# V7.net
KiCad netlist of a schematic drawn in Altium Designer
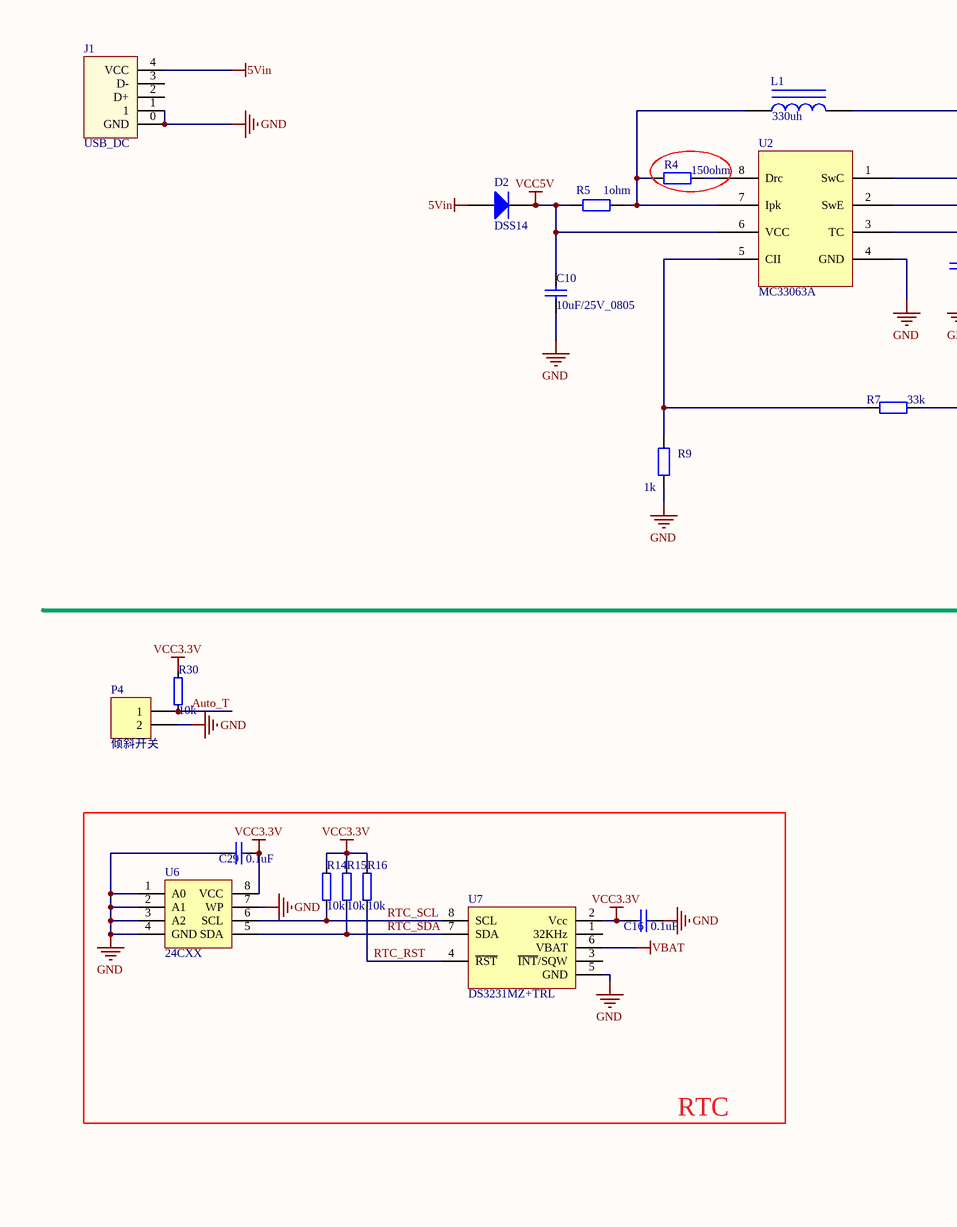
[diagram p0: V7.SchDoc, left]
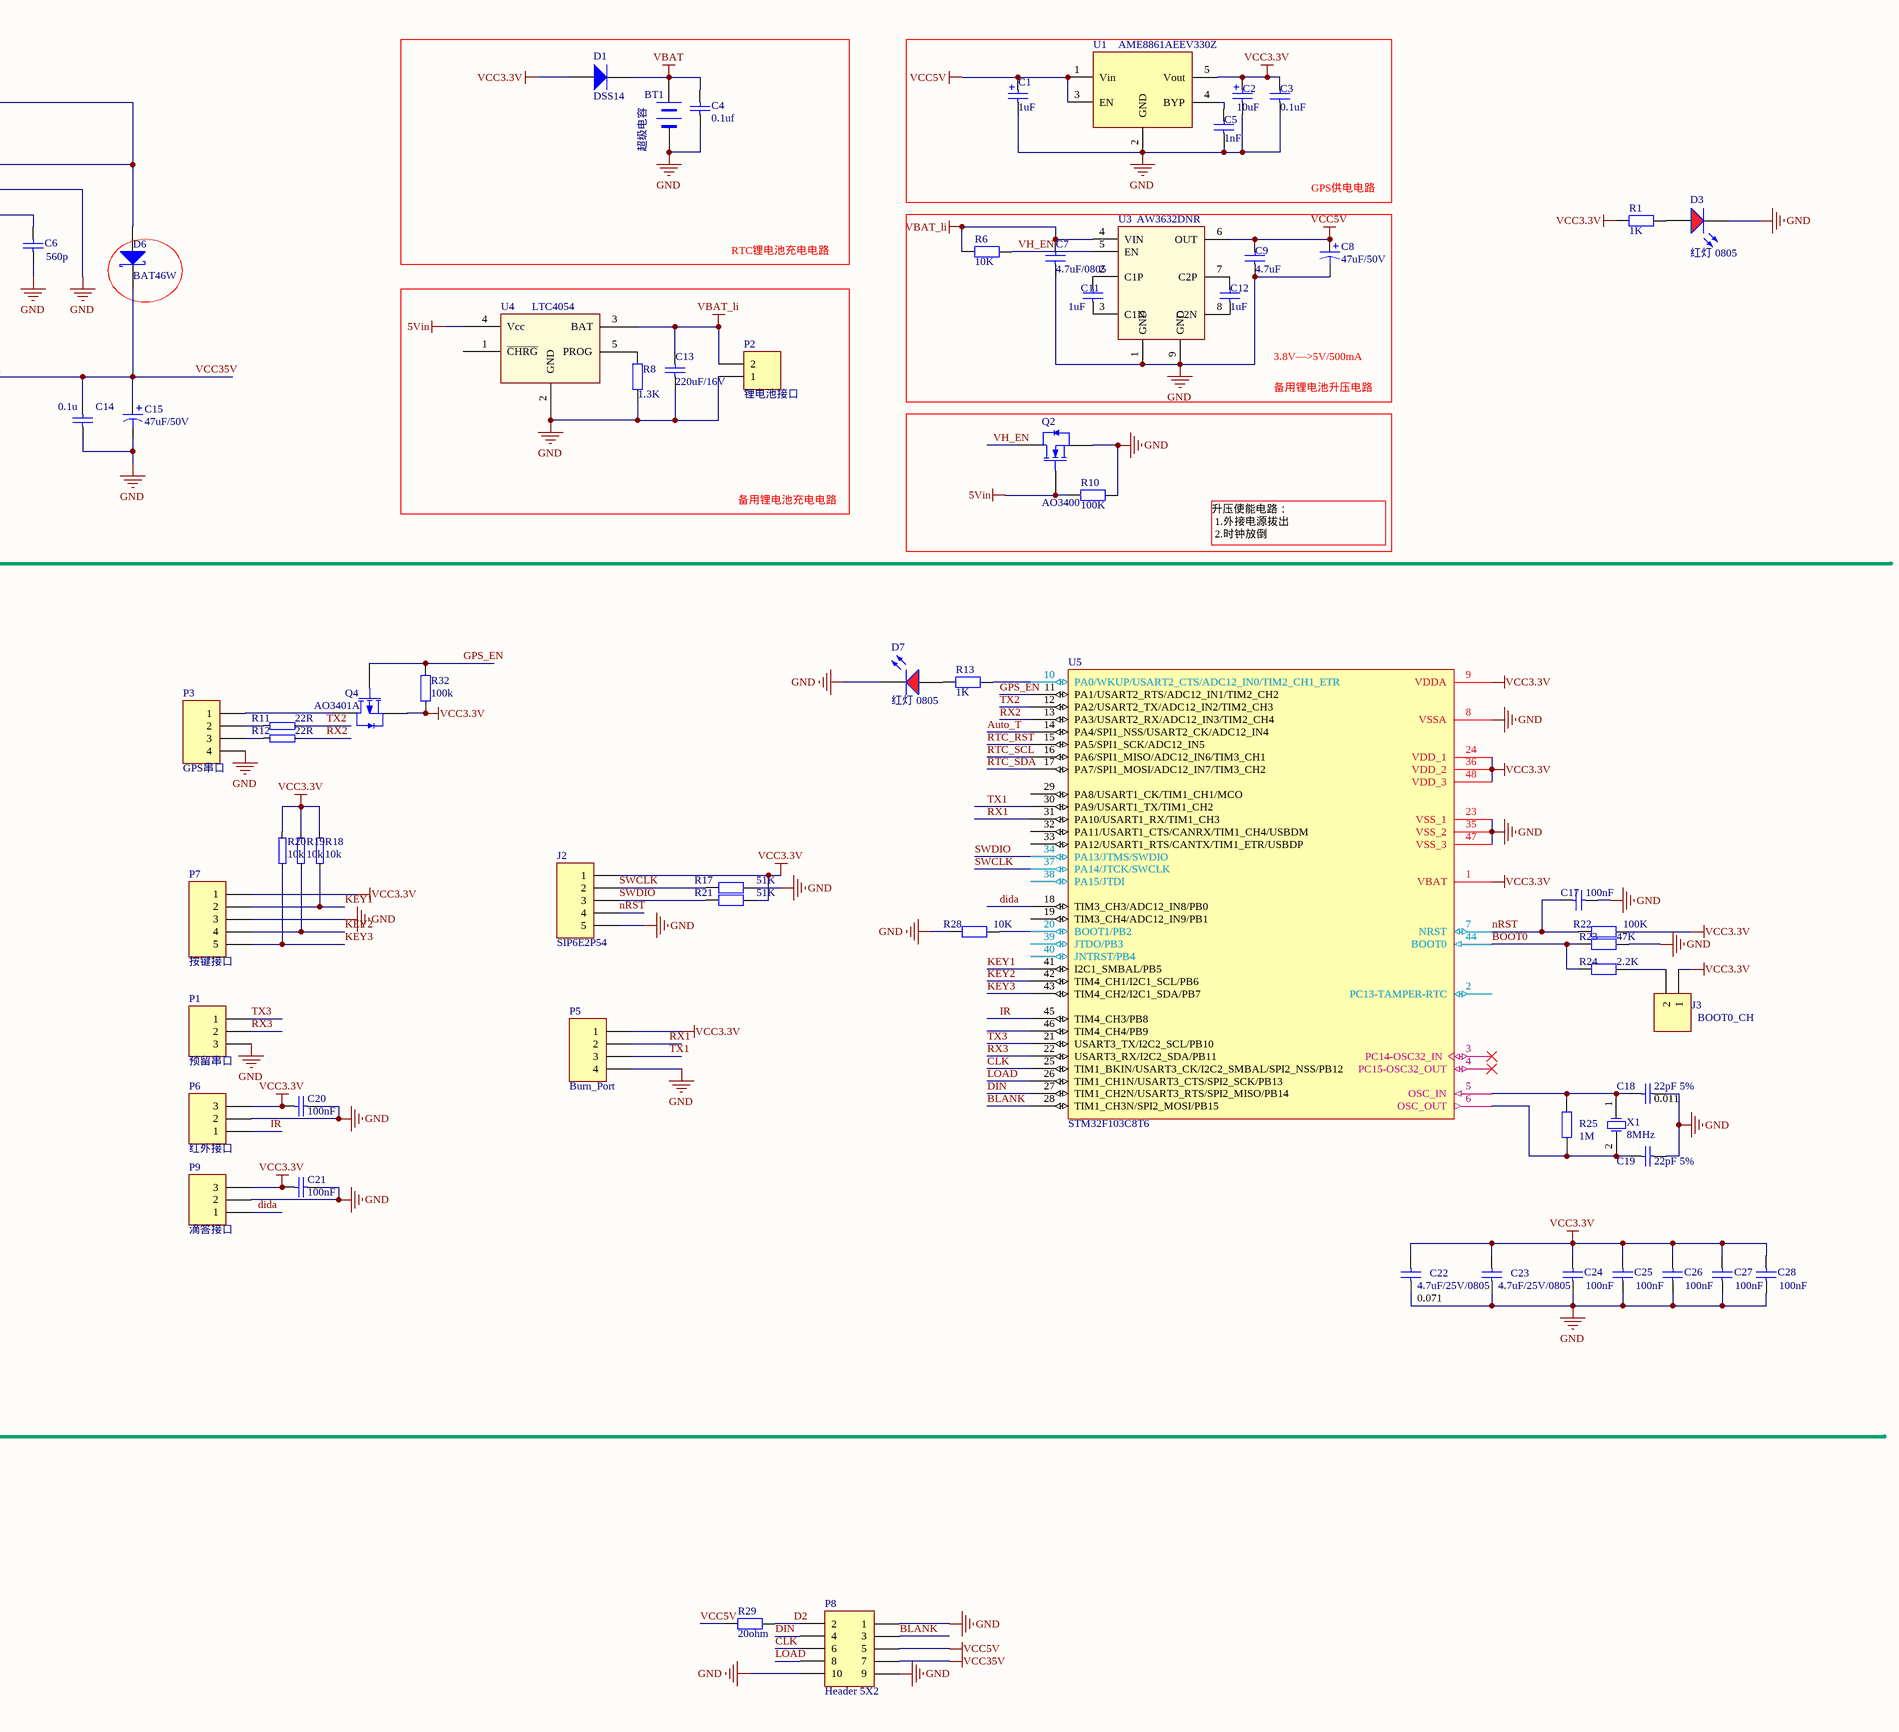
[diagram p1: V7.SchDoc, right]

(export (version "E")
  (design (tool "Eeschema 10.0.6"))
  (components
    (comp (ref "BT1")
      (value "超级电容")
      (footprint "SF-3R3-S104Z")
      (description "Battery")
      (libsource (lib "常用1") (part "BATTERY"))
    )
    (comp (ref "C1")
      (value "1uF")
      (footprint "C1608(CC0603)")
      (description "Polarized Capacitor (Axial)")
      (fields (field (name "PUBLISHER") "Altium Limited"))
      (libsource (lib "Miscellaneous Devices") (part "Cap Pol2"))
    )
    (comp (ref "C2")
      (value "10uF")
      (footprint "C2012(CC0805)")
      (description "Polarized Capacitor (Axial)")
      (fields (field (name "PUBLISHER") "Altium Limited"))
      (libsource (lib "Miscellaneous Devices") (part "Cap Pol2"))
    )
    (comp (ref "C3")
      (value "0.1uF")
      (footprint "C1608(CC0603)")
      (description "Capacitor")
      (fields (field (name "PUBLISHER") "Altium Limited"))
      (libsource (lib "Miscellaneous Devices") (part "Cap"))
    )
    (comp (ref "C4")
      (value "0.1uf")
      (footprint "C1608(CC0603)")
      (description "Capacitor")
      (fields (field (name "PUBLISHER") "Altium Limited"))
      (libsource (lib "Miscellaneous Devices") (part "Cap"))
    )
    (comp (ref "C5")
      (value "1nF")
      (footprint "C1608(CC0603)")
      (description "Capacitor")
      (fields (field (name "PUBLISHER") "Altium Limited"))
      (libsource (lib "Miscellaneous Devices") (part "Cap"))
    )
    (comp (ref "C6")
      (value "560p")
      (footprint "C1608(CC0603)")
      (description "Capacitor")
      (fields (field (name "PUBLISHER") "Altium Limited"))
      (libsource (lib "Miscellaneous Devices") (part "Cap"))
    )
    (comp (ref "C7")
      (value "4.7uF/0805")
      (footprint "C1608(CC0603)")
      (description "Capacitor")
      (fields (field (name "PUBLISHER") "Altium Limited"))
      (libsource (lib "Miscellaneous Devices") (part "Cap"))
    )
    (comp (ref "C8")
      (value "47uF/50V")
      (footprint "铝电解电容6.3")
      (description "E型")
      (fields (field (name "PUBLISHER") "Altium Limited"))
      (libsource (lib "Miscellaneous Devices") (part "Cap Pol1"))
    )
    (comp (ref "C9")
      (value "4.7uF")
      (footprint "C1608(CC0603)")
      (description "Capacitor")
      (fields (field (name "PUBLISHER") "Altium Limited"))
      (libsource (lib "Miscellaneous Devices") (part "Cap"))
    )
    (comp (ref "C10")
      (value "10uF/25V_0805")
      (footprint "C2012(CC0805)")
      (description "Capacitor")
      (fields (field (name "PUBLISHER") "Altium Limited"))
      (libsource (lib "Miscellaneous Devices") (part "Cap"))
    )
    (comp (ref "C11")
      (value "1uF")
      (footprint "C1608(CC0603)")
      (description "Capacitor")
      (fields (field (name "PUBLISHER") "Altium Limited"))
      (libsource (lib "Miscellaneous Devices") (part "Cap"))
    )
    (comp (ref "C12")
      (value "1uF")
      (footprint "C1608(CC0603)")
      (description "Capacitor")
      (fields (field (name "PUBLISHER") "Altium Limited"))
      (libsource (lib "Miscellaneous Devices") (part "Cap"))
    )
    (comp (ref "C13")
      (value "220uF/16V")
      (footprint "C2012(CC0805)")
      (description "Capacitor")
      (fields (field (name "PUBLISHER") "Altium Limited"))
      (libsource (lib "Miscellaneous Devices") (part "Cap"))
    )
    (comp (ref "C14")
      (value "0.1u")
      (footprint "C1608(CC0603)")
      (description "Capacitor")
      (fields (field (name "PUBLISHER") "Altium Limited"))
      (libsource (lib "Miscellaneous Devices") (part "Cap"))
    )
    (comp (ref "C15")
      (value "47uF/50V")
      (footprint "铝电解电容6.3")
      (description "E型")
      (fields (field (name "PUBLISHER") "Altium Limited"))
      (libsource (lib "Miscellaneous Devices") (part "Cap Pol1"))
    )
    (comp (ref "C16")
      (value "0.1uF")
      (footprint "C1608(CC0603)")
      (description "Capacitor")
      (fields (field (name "PUBLISHER") "Altium Limited"))
      (libsource (lib "Miscellaneous Devices") (part "Cap"))
    )
    (comp (ref "C17")
      (value "100nF")
      (footprint "C1608(CC0603)")
      (description "Capacitor")
      (fields (field (name "Comment") "1nF") (field (name "PUBLISHER") "Altium Limited"))
      (libsource (lib "Miscellaneous Devices") (part "Cap"))
    )
    (comp (ref "C18")
      (value "22pF 5%")
      (footprint "C1608(CC0603)")
      (description "Capacitor")
      (fields (field (name "PUBLISHER") "Altium Limited"))
      (libsource (lib "") (part "Cap_1"))
    )
    (comp (ref "C19")
      (value "22pF 5%")
      (footprint "C1608(CC0603)")
      (description "Capacitor")
      (fields (field (name "PUBLISHER") "Altium Limited"))
      (libsource (lib "") (part "Cap_1"))
    )
    (comp (ref "C20")
      (value "100nF")
      (footprint "C1608(CC0603)")
      (description "Capacitor")
      (fields (field (name "PUBLISHER") "Altium Limited"))
      (libsource (lib "Miscellaneous Devices") (part "Cap"))
    )
    (comp (ref "C21")
      (value "100nF")
      (footprint "C1608(CC0603)")
      (description "Capacitor")
      (fields (field (name "PUBLISHER") "Altium Limited"))
      (libsource (lib "Miscellaneous Devices") (part "Cap"))
    )
    (comp (ref "C22")
      (value "4.7uF/25V/0805")
      (footprint "C2012(CC0805)")
      (description "Capacitor")
      (fields (field (name "PUBLISHER") "Altium Limited"))
      (libsource (lib "Miscellaneous Devices") (part "Cap"))
    )
    (comp (ref "C23")
      (value "4.7uF/25V/0805")
      (footprint "C2012(CC0805)")
      (description "Capacitor")
      (fields (field (name "PUBLISHER") "Altium Limited"))
      (libsource (lib "Miscellaneous Devices") (part "Cap"))
    )
    (comp (ref "C24")
      (value "100nF")
      (footprint "C1608(CC0603)")
      (description "Capacitor")
      (fields (field (name "PUBLISHER") "Altium Limited"))
      (libsource (lib "Miscellaneous Devices") (part "Cap"))
    )
    (comp (ref "C25")
      (value "100nF")
      (footprint "C1608(CC0603)")
      (description "Capacitor")
      (fields (field (name "PUBLISHER") "Altium Limited"))
      (libsource (lib "Miscellaneous Devices") (part "Cap"))
    )
    (comp (ref "C26")
      (value "100nF")
      (footprint "C1608(CC0603)")
      (description "Capacitor")
      (fields (field (name "PUBLISHER") "Altium Limited"))
      (libsource (lib "Miscellaneous Devices") (part "Cap"))
    )
    (comp (ref "C27")
      (value "100nF")
      (footprint "C1608(CC0603)")
      (description "Capacitor")
      (fields (field (name "PUBLISHER") "Altium Limited"))
      (libsource (lib "Miscellaneous Devices") (part "Cap"))
    )
    (comp (ref "C28")
      (value "100nF")
      (footprint "C1608(CC0603)")
      (description "Capacitor")
      (fields (field (name "PUBLISHER") "Altium Limited"))
      (libsource (lib "Miscellaneous Devices") (part "Cap"))
    )
    (comp (ref "C29")
      (value "0.1uF")
      (footprint "C1608(CC0603)")
      (description "Capacitor")
      (fields (field (name "PUBLISHER") "Altium Limited"))
      (libsource (lib "Miscellaneous Devices") (part "Cap"))
    )
    (comp (ref "D1")
      (value "DSS14")
      (footprint "LC-SOD-123F")
      (description "肖特基二极管")
      (libsource (lib "Miscellaneous Devices LC") (part "SOD-123 B5819W  SL"))
    )
    (comp (ref "D2")
      (value "DSS14")
      (footprint "LC-SOD-123F")
      (description "肖特基二极管")
      (libsource (lib "Miscellaneous Devices LC") (part "SOD-123 B5819W  SL"))
    )
    (comp (ref "D3")
      (value "红灯 0805")
      (footprint "LC-0805_LED_S1")
      (description "发光二极管")
      (libsource (lib "Miscellaneous Devices LC") (part "0805 红灯"))
    )
    (comp (ref "D6")
      (value "BAT46W")
      (footprint "INDM2716X11N")
      (description "Schottky Rectifier")
      (fields (field (name "PUBLISHER") "Altium Limited"))
      (libsource (lib "Miscellaneous Devices") (part "Diode 10TQ045"))
    )
    (comp (ref "D7")
      (value "红灯 0805")
      (footprint "LC-0805_LED_S1")
      (description "发光二极管")
      (libsource (lib "Miscellaneous Devices LC") (part "0805 红灯"))
    )
    (comp (ref "J1") (value "USB_DC") (footprint "USB_DC") (libsource (lib "个人") (part "USB_DC")))
    (comp (ref "J2")
      (value "SIP6E2P54")
      (footprint "HDR1X5")
      (description "Header, 5-Pin")
      (fields (field (name "PUBLISHER") "Altium Limited"))
      (libsource (lib "Miscellaneous Connectors") (part "Header 5"))
    )
    (comp (ref "J3")
      (value "BOOT0_CH")
      (footprint "HDR1X2")
      (description "Header, 2-Pin")
      (fields (field (name "PUBLISHER") "Altium Limited"))
      (libsource (lib "") (part "Header 2_1"))
    )
    (comp (ref "L1")
      (value "330uh")
      (footprint "INDM7070X40N")
      (description "7*7")
      (fields (field (name "PUBLISHER") "Altium Limited"))
      (libsource (lib "Miscellaneous Devices") (part "Inductor Iron"))
    )
    (comp (ref "P1")
      (value "预留串口")
      (footprint "HDR1X3")
      (description "Header, 3-Pin")
      (fields (field (name "PUBLISHER") "Altium Limited"))
      (libsource (lib "") (part "Header 3_1"))
    )
    (comp (ref "P2")
      (value "锂电池接口")
      (footprint "XH2.54-2A")
      (description "Header, 2-Pin")
      (fields (field (name "PUBLISHER") "Altium Limited"))
      (libsource (lib "Miscellaneous Connectors") (part "Header 2"))
    )
    (comp (ref "P3")
      (value "GPS串口")
      (footprint "HDR1X4")
      (description "Header, 4-Pin")
      (fields (field (name "PUBLISHER") "Altium Limited"))
      (libsource (lib "Miscellaneous Connectors") (part "Header 4"))
    )
    (comp (ref "P4")
      (value "倾斜开关")
      (footprint "HDR1X2")
      (description "Header, 2-Pin")
      (fields (field (name "PUBLISHER") "Altium Limited"))
      (libsource (lib "") (part "Header 2_1"))
    )
    (comp (ref "P5")
      (value "Burn_Port")
      (footprint "HDR1X4")
      (description "Header, 4-Pin")
      (fields (field (name "PUBLISHER") "Altium Limited"))
      (libsource (lib "Miscellaneous Connectors") (part "Header 4"))
    )
    (comp (ref "P6")
      (value "红外接口")
      (footprint "HDR1X3")
      (description "Header, 3-Pin")
      (fields (field (name "PUBLISHER") "Altium Limited"))
      (libsource (lib "Miscellaneous Connectors") (part "Header 3"))
    )
    (comp (ref "P7")
      (value "按键接口")
      (footprint "XH2.54-5A")
      (description "Header, 5-Pin")
      (fields (field (name "PUBLISHER") "Altium Limited"))
      (libsource (lib "Miscellaneous Connectors") (part "Header 5"))
    )
    (comp (ref "P8")
      (value "Header 5X2")
      (footprint "HDR2X5")
      (description "Header, 5-Pin, Dual row")
      (fields (field (name "PUBLISHER") "Altium Limited"))
      (libsource (lib "Miscellaneous Connectors") (part "Header 5X2"))
    )
    (comp (ref "P9")
      (value "滴答接口")
      (footprint "HDR1X3")
      (description "Header, 3-Pin")
      (fields (field (name "PUBLISHER") "Altium Limited"))
      (libsource (lib "Miscellaneous Connectors") (part "Header 3"))
    )
    (comp (ref "Q2")
      (value "AO3400")
      (footprint "LC-SOT-23-3L")
      (description "MOS(场效应管)")
      (libsource (lib "Miscellaneous Devices LC") (part "AO3400A N道沟 X0YV1T SOT-23"))
    )
    (comp (ref "Q4")
      (value "AO3401A")
      (footprint "LC-SOT-23-3L")
      (description "MOS(场效应管)")
      (libsource (lib "Miscellaneous Devices LC") (part "AO3401A P道沟 X13A15 SOT-23"))
    )
    (comp (ref "R1")
      (value "1K")
      (footprint "C1608(CC0603)")
      (description "Resistor")
      (fields (field (name "PUBLISHER") "Altium Limited"))
      (libsource (lib "") (part "Res2_2"))
    )
    (comp (ref "R4")
      (value "150ohm")
      (footprint "C1608(CC0603)")
      (description "Resistor")
      (fields (field (name "PUBLISHER") "Altium Limited"))
      (libsource (lib "") (part "Res2_2"))
    )
    (comp (ref "R5")
      (value "1ohm")
      (footprint "C1608(CC0603)")
      (description "Resistor")
      (fields (field (name "PUBLISHER") "Altium Limited"))
      (libsource (lib "") (part "Res2_2"))
    )
    (comp (ref "R6")
      (value "10K")
      (footprint "C1608(CC0603)")
      (description "Resistor")
      (fields (field (name "PUBLISHER") "Altium Limited"))
      (libsource (lib "") (part "Res2_2"))
    )
    (comp (ref "R7")
      (value "33k")
      (footprint "C1608(CC0603)")
      (description "Resistor")
      (fields (field (name "PUBLISHER") "Altium Limited"))
      (libsource (lib "") (part "Res2_2"))
    )
    (comp (ref "R8")
      (value "1.3K")
      (footprint "C1608(CC0603)")
      (description "Resistor")
      (fields (field (name "PUBLISHER") "Altium Limited"))
      (libsource (lib "Miscellaneous Devices") (part "Res2"))
    )
    (comp (ref "R9")
      (value "1k")
      (footprint "C1608(CC0603)")
      (description "Resistor")
      (fields (field (name "PUBLISHER") "Altium Limited"))
      (libsource (lib "") (part "Res2_3"))
    )
    (comp (ref "R10")
      (value "100K")
      (footprint "C1608(CC0603)")
      (description "Resistor")
      (fields (field (name "PUBLISHER") "Altium Limited"))
      (libsource (lib "") (part "Res2_1"))
    )
    (comp (ref "R11") (value "22R") (footprint "C1608(CC0603)") (libsource (lib "SCHS") (part "RES5")))
    (comp (ref "R12") (value "22R") (footprint "C1608(CC0603)") (libsource (lib "SCHS") (part "RES5")))
    (comp (ref "R13")
      (value "1K")
      (footprint "C1608(CC0603)")
      (description "Resistor")
      (fields (field (name "PUBLISHER") "Altium Limited"))
      (libsource (lib "") (part "Res2_1"))
    )
    (comp (ref "R14") (value "10k") (footprint "C1608(CC0603)") (libsource (lib "SCHS") (part "RES5")))
    (comp (ref "R15") (value "10k") (footprint "C1608(CC0603)") (libsource (lib "SCHS") (part "RES5")))
    (comp (ref "R16") (value "10k") (footprint "C1608(CC0603)") (libsource (lib "SCHS") (part "RES5")))
    (comp (ref "R17")
      (value "51K")
      (footprint "C1608(CC0603)")
      (description "Resistor")
      (fields (field (name "PUBLISHER") "Altium Limited"))
      (libsource (lib "") (part "Res2_1"))
    )
    (comp (ref "R18") (value "10k") (footprint "C1608(CC0603)") (libsource (lib "SCHS") (part "RES5")))
    (comp (ref "R19") (value "10k") (footprint "C1608(CC0603)") (libsource (lib "SCHS") (part "RES5")))
    (comp (ref "R20") (value "10k") (footprint "C1608(CC0603)") (libsource (lib "SCHS") (part "RES5")))
    (comp (ref "R21")
      (value "51K")
      (footprint "C1608(CC0603)")
      (description "Resistor")
      (fields (field (name "PUBLISHER") "Altium Limited"))
      (libsource (lib "") (part "Res2_1"))
    )
    (comp (ref "R22")
      (value "100K")
      (footprint "C1608(CC0603)")
      (description "Resistor")
      (fields (field (name "Comment") "100R") (field (name "PUBLISHER") "Altium Limited"))
      (libsource (lib "") (part "Res2_2"))
    )
    (comp (ref "R23")
      (value "47K")
      (footprint "C1608(CC0603)")
      (description "Resistor")
      (fields (field (name "PUBLISHER") "Altium Limited"))
      (libsource (lib "") (part "Res2_1"))
    )
    (comp (ref "R24")
      (value "2.2K")
      (footprint "C1608(CC0603)")
      (description "Resistor")
      (fields (field (name "PUBLISHER") "Altium Limited"))
      (libsource (lib "") (part "Res2_2"))
    )
    (comp (ref "R25")
      (value "1M")
      (footprint "C1608(CC0603)")
      (description "Resistor")
      (fields (field (name "PUBLISHER") "Altium Limited"))
      (libsource (lib "Miscellaneous Devices") (part "Res2"))
    )
    (comp (ref "R28")
      (value "10K")
      (footprint "C1608(CC0603)")
      (description "Resistor")
      (fields (field (name "Comment") "100R") (field (name "PUBLISHER") "Altium Limited"))
      (libsource (lib "") (part "Res2_2"))
    )
    (comp (ref "R29")
      (value "20ohm")
      (footprint "C1608(CC0603)")
      (description "Resistor")
      (fields (field (name "PUBLISHER") "Altium Limited"))
      (libsource (lib "") (part "Res2_3"))
    )
    (comp (ref "R30") (value "10k") (footprint "C1608(CC0603)") (libsource (lib "SCHS") (part "RES5")))
    (comp (ref "R32")
      (value "100k")
      (footprint "C1608(CC0603)")
      (description "Resistor")
      (fields (field (name "PUBLISHER") "Altium Limited"))
      (libsource (lib "") (part "Res2_1"))
    )
    (comp (ref "U1")
      (value "AME8861AEEV330Z")
      (footprint "SOT23-5")
      (description "MIC5205-3.3BM5")
      (libsource (lib "个人") (part "MIC5205-3.3BM5"))
    )
    (comp (ref "U2")
      (value "MC33063A")
      (footprint "LC-SOP-8_150mil")
      (libsource (lib "MC33063A") (part "MC330"))
    )
    (comp (ref "U3") (value "AW3632DNR") (footprint "DFN_8L") (libsource (lib "个人") (part "AW3632DNR")))
    (comp (ref "U4") (value "LTC4054") (footprint "LC-SOT-23-5") (libsource (lib "个人") (part "LTC4054")))
    (comp (ref "U5")
      (value "STM32F103C8T6")
      (footprint "LC-LQFP-48_7x7x05P")
      (description "STM32 ARM-based 32-bit MCU with 64 Kbytes Flash, 48-pin LQFP, Industrial Temperature")
      (fields (field (name "PUBLISHER") "*"))
      (libsource (lib "个人") (part "STM32F103C8T6"))
    )
    (comp (ref "U6") (value "24CXX") (footprint "LC-SOP-8_150mil") (libsource (lib "个人") (part "24CXX")))
    (comp (ref "U7")
      (value "DS3231MZ+TRL")
      (footprint "LC-SOIC-8_150mil")
      (libsource (lib "个人") (part "DS3231MZ+TRL"))
    )
    (comp (ref "X1")
      (value "8MHz")
      (footprint "XTAL-5032")
      (description "Crystal Oscillator")
      (fields (field (name "PUBLISHER") "Altium Limited"))
      (libsource (lib "Miscellaneous Devices") (part "XTAL"))
    )
  )
  (nets
    (net (code "1") (name "/Auto_T") (class "Default")
      (node (ref "P4") (pin "1") (pinfunction "1_1") (pintype "passive"))
      (node (ref "R30") (pin "2") (pintype "passive"))
      (node (ref "U5") (pin "14") (pinfunction "PA4/SPI1_NSS/USART2_CK/ADC12_IN4_14") (pintype "bidirectional"))
    )
    (net (code "2") (name "/BLANK") (class "Default")
      (node (ref "P8") (pin "3") (pinfunction "3_3") (pintype "passive"))
      (node (ref "U5") (pin "28") (pinfunction "TIM1_CH3N/SPI2_MOSI/PB15_28") (pintype "bidirectional"))
    )
    (net (code "3") (name "/BOOT0") (class "Default")
      (node (ref "R23") (pin "2") (pinfunction "2_2") (pintype "passive"))
      (node (ref "R24") (pin "1") (pinfunction "1_1") (pintype "passive"))
      (node (ref "U5") (pin "44") (pinfunction "BOOT0_44") (pintype "input"))
    )
    (net (code "4") (name "/CLK") (class "Default")
      (node (ref "P8") (pin "6") (pinfunction "6_6") (pintype "passive"))
      (node (ref "U5") (pin "25") (pinfunction "TIM1_BKIN/USART3_CK/I2C2_SMBAL/SPI2_NSS/PB12_25") (pintype "bidirectional"))
    )
    (net (code "5") (name "/D2") (class "Default")
      (node (ref "P8") (pin "2") (pinfunction "2_2") (pintype "passive"))
      (node (ref "R29") (pin "2") (pinfunction "2_2") (pintype "passive"))
    )
    (net (code "6") (name "/DIN") (class "Default")
      (node (ref "P8") (pin "4") (pinfunction "4_4") (pintype "passive"))
      (node (ref "U5") (pin "27") (pinfunction "TIM1_CH2N/USART3_RTS/SPI2_MISO/PB14_27") (pintype "bidirectional"))
    )
    (net (code "7") (name "/GPS_EN") (class "Default")
      (node (ref "Q4") (pin "1") (pinfunction "G_1") (pintype "passive"))
      (node (ref "R32") (pin "1") (pinfunction "1_1") (pintype "passive"))
      (node (ref "U5") (pin "11") (pinfunction "PA1/USART2_RTS/ADC12_IN1/TIM2_CH2_11") (pintype "bidirectional"))
    )
    (net (code "8") (name "/IR") (class "Default")
      (node (ref "P6") (pin "1") (pinfunction "1_1") (pintype "passive"))
      (node (ref "U5") (pin "45") (pinfunction "TIM4_CH3/PB8_45") (pintype "bidirectional"))
    )
    (net (code "9") (name "/KEY1") (class "Default")
      (node (ref "P7") (pin "2") (pinfunction "2_2") (pintype "passive"))
      (node (ref "R18") (pin "2") (pintype "passive"))
      (node (ref "U5") (pin "41") (pinfunction "I2C1_SMBAL/PB5_41") (pintype "bidirectional"))
    )
    (net (code "10") (name "/KEY2") (class "Default")
      (node (ref "P7") (pin "4") (pinfunction "4_4") (pintype "passive"))
      (node (ref "R19") (pin "2") (pintype "passive"))
      (node (ref "U5") (pin "42") (pinfunction "TIM4_CH1/I2C1_SCL/PB6_42") (pintype "bidirectional"))
    )
    (net (code "11") (name "/KEY3") (class "Default")
      (node (ref "P7") (pin "5") (pinfunction "5_5") (pintype "passive"))
      (node (ref "R20") (pin "2") (pintype "passive"))
      (node (ref "U5") (pin "43") (pinfunction "TIM4_CH2/I2C1_SDA/PB7_43") (pintype "bidirectional"))
    )
    (net (code "12") (name "/LOAD") (class "Default")
      (node (ref "P8") (pin "8") (pinfunction "8_8") (pintype "passive"))
      (node (ref "U5") (pin "26") (pinfunction "TIM1_CH1N/USART3_CTS/SPI2_SCK/PB13_26") (pintype "bidirectional"))
    )
    (net (code "13") (name "/RTC_RST") (class "Default")
      (node (ref "R16") (pin "2") (pintype "passive"))
      (node (ref "U5") (pin "15") (pinfunction "PA5/SPI1_SCK/ADC12_IN5_15") (pintype "bidirectional"))
      (node (ref "U7") (pin "4") (pinfunction "~{RST}_4") (pintype "passive"))
    )
    (net (code "14") (name "/RTC_SCL") (class "Default")
      (node (ref "R14") (pin "2") (pintype "passive"))
      (node (ref "U5") (pin "16") (pinfunction "PA6/SPI1_MISO/ADC12_IN6/TIM3_CH1_16") (pintype "bidirectional"))
      (node (ref "U6") (pin "6") (pinfunction "SCL_6") (pintype "passive"))
      (node (ref "U7") (pin "8") (pinfunction "SCL_8") (pintype "passive"))
    )
    (net (code "15") (name "/RTC_SDA") (class "Default")
      (node (ref "R15") (pin "2") (pintype "passive"))
      (node (ref "U5") (pin "17") (pinfunction "PA7/SPI1_MOSI/ADC12_IN7/TIM3_CH2_17") (pintype "bidirectional"))
      (node (ref "U6") (pin "5") (pinfunction "SDA_5") (pintype "passive"))
      (node (ref "U7") (pin "7") (pinfunction "SDA_7") (pintype "passive"))
    )
    (net (code "16") (name "/RX1") (class "Default")
      (node (ref "P5") (pin "2") (pinfunction "2_2") (pintype "passive"))
      (node (ref "U5") (pin "31") (pinfunction "PA10/USART1_RX/TIM1_CH3_31") (pintype "bidirectional"))
    )
    (net (code "17") (name "/RX2") (class "Default")
      (node (ref "R12") (pin "2") (pintype "passive"))
      (node (ref "U5") (pin "13") (pinfunction "PA3/USART2_RX/ADC12_IN3/TIM2_CH4_13") (pintype "bidirectional"))
    )
    (net (code "18") (name "/RX3") (class "Default")
      (node (ref "P1") (pin "2") (pinfunction "2_2") (pintype "passive"))
      (node (ref "U5") (pin "22") (pinfunction "USART3_RX/I2C2_SDA/PB11_22") (pintype "bidirectional"))
    )
    (net (code "19") (name "/SWCLK") (class "Default")
      (node (ref "J2") (pin "2") (pinfunction "2_2") (pintype "passive"))
      (node (ref "R17") (pin "2") (pinfunction "2_2") (pintype "passive"))
      (node (ref "U5") (pin "37") (pinfunction "PA14/JTCK/SWCLK_37") (pintype "bidirectional"))
    )
    (net (code "20") (name "/SWDIO") (class "Default")
      (node (ref "J2") (pin "3") (pinfunction "3_3") (pintype "passive"))
      (node (ref "R21") (pin "2") (pinfunction "2_2") (pintype "passive"))
      (node (ref "U5") (pin "34") (pinfunction "PA13/JTMS/SWDIO_34") (pintype "bidirectional"))
    )
    (net (code "21") (name "/TX1") (class "Default")
      (node (ref "P5") (pin "3") (pinfunction "3_3") (pintype "passive"))
      (node (ref "U5") (pin "30") (pinfunction "PA9/USART1_TX/TIM1_CH2_30") (pintype "bidirectional"))
    )
    (net (code "22") (name "/TX2") (class "Default")
      (node (ref "R11") (pin "2") (pintype "passive"))
      (node (ref "U5") (pin "12") (pinfunction "PA2/USART2_TX/ADC12_IN2/TIM2_CH3_12") (pintype "bidirectional"))
    )
    (net (code "23") (name "/TX3") (class "Default")
      (node (ref "P1") (pin "1") (pinfunction "1_1") (pintype "passive"))
      (node (ref "U5") (pin "21") (pinfunction "USART3_TX/I2C2_SCL/PB10_21") (pintype "bidirectional"))
    )
    (net (code "24") (name "/VH_EN") (class "Default")
      (node (ref "Q2") (pin "3") (pinfunction "D_3") (pintype "passive"))
      (node (ref "R6") (pin "2") (pinfunction "2_2") (pintype "passive"))
      (node (ref "U3") (pin "5") (pinfunction "EN_5") (pintype "passive"))
    )
    (net (code "25") (name "/dida") (class "Default")
      (node (ref "P9") (pin "1") (pinfunction "1_1") (pintype "passive"))
      (node (ref "U5") (pin "18") (pinfunction "TIM3_CH3/ADC12_IN8/PB0_18") (pintype "bidirectional"))
    )
    (net (code "26") (name "/nRST") (class "Default")
      (node (ref "C17") (pin "1") (pinfunction "1_1") (pintype "passive"))
      (node (ref "J2") (pin "4") (pinfunction "4_4") (pintype "passive"))
      (node (ref "R22") (pin "1") (pinfunction "1_1") (pintype "passive"))
      (node (ref "U5") (pin "7") (pinfunction "NRST_7") (pintype "bidirectional"))
    )
    (net (code "27") (name "5Vin") (class "Default")
      (node (ref "D2") (pin "1") (pinfunction "A_1") (pintype "passive"))
      (node (ref "J1") (pin "4") (pinfunction "VCC_4") (pintype "passive"))
      (node (ref "Q2") (pin "1") (pinfunction "G_1") (pintype "passive"))
      (node (ref "R10") (pin "2") (pinfunction "2_2") (pintype "passive"))
      (node (ref "U4") (pin "4") (pinfunction "Vcc_4") (pintype "passive"))
    )
    (net (code "28") (name "GND") (class "Default")
      (node (ref "BT1") (pin "2") (pinfunction "-_2") (pintype "passive"))
      (node (ref "C1") (pin "2") (pinfunction "2_2") (pintype "passive"))
      (node (ref "C10") (pin "1") (pinfunction "1_1") (pintype "passive"))
      (node (ref "C13") (pin "1") (pinfunction "1_1") (pintype "passive"))
      (node (ref "C14") (pin "1") (pinfunction "1_1") (pintype "passive"))
      (node (ref "C15") (pin "2") (pintype "passive"))
      (node (ref "C16") (pin "1") (pinfunction "1_1") (pintype "passive"))
      (node (ref "C17") (pin "2") (pinfunction "2_2") (pintype "passive"))
      (node (ref "C18") (pin "1") (pinfunction "1_1") (pintype "passive"))
      (node (ref "C19") (pin "1") (pinfunction "1_1") (pintype "passive"))
      (node (ref "C2") (pin "2") (pinfunction "2_2") (pintype "passive"))
      (node (ref "C20") (pin "2") (pinfunction "2_2") (pintype "passive"))
      (node (ref "C21") (pin "2") (pinfunction "2_2") (pintype "passive"))
      (node (ref "C22") (pin "1") (pinfunction "1_1") (pintype "passive"))
      (node (ref "C23") (pin "1") (pinfunction "1_1") (pintype "passive"))
      (node (ref "C24") (pin "2") (pinfunction "2_2") (pintype "passive"))
      (node (ref "C25") (pin "2") (pinfunction "2_2") (pintype "passive"))
      (node (ref "C26") (pin "2") (pinfunction "2_2") (pintype "passive"))
      (node (ref "C27") (pin "2") (pinfunction "2_2") (pintype "passive"))
      (node (ref "C28") (pin "2") (pinfunction "2_2") (pintype "passive"))
      (node (ref "C29") (pin "2") (pinfunction "2_2") (pintype "passive"))
      (node (ref "C3") (pin "1") (pinfunction "1_1") (pintype "passive"))
      (node (ref "C4") (pin "1") (pinfunction "1_1") (pintype "passive"))
      (node (ref "C5") (pin "1") (pinfunction "1_1") (pintype "passive"))
      (node (ref "C6") (pin "2") (pinfunction "2_2") (pintype "passive"))
      (node (ref "C7") (pin "2") (pinfunction "2_2") (pintype "passive"))
      (node (ref "C8") (pin "2") (pintype "passive"))
      (node (ref "C9") (pin "2") (pinfunction "2_2") (pintype "passive"))
      (node (ref "D3") (pin "K") (pinfunction "K_K") (pintype "passive"))
      (node (ref "D7") (pin "K") (pinfunction "K_K") (pintype "passive"))
      (node (ref "J1") (pin "0") (pinfunction "GND_0") (pintype "passive"))
      (node (ref "J1") (pin "1") (pinfunction "1_1") (pintype "passive"))
      (node (ref "J2") (pin "5") (pinfunction "5_5") (pintype "passive"))
      (node (ref "P1") (pin "3") (pinfunction "3_3") (pintype "passive"))
      (node (ref "P2") (pin "1") (pinfunction "1_1") (pintype "passive"))
      (node (ref "P3") (pin "4") (pinfunction "4_4") (pintype "passive"))
      (node (ref "P4") (pin "2") (pinfunction "2_2") (pintype "passive"))
      (node (ref "P5") (pin "4") (pinfunction "4_4") (pintype "passive"))
      (node (ref "P6") (pin "2") (pinfunction "2_2") (pintype "passive"))
      (node (ref "P7") (pin "3") (pinfunction "3_3") (pintype "passive"))
      (node (ref "P8") (pin "1") (pinfunction "1_1") (pintype "passive"))
      (node (ref "P8") (pin "10") (pinfunction "10_10") (pintype "passive"))
      (node (ref "P8") (pin "9") (pinfunction "9_9") (pintype "passive"))
      (node (ref "P9") (pin "2") (pinfunction "2_2") (pintype "passive"))
      (node (ref "Q2") (pin "2") (pinfunction "S_2") (pintype "passive"))
      (node (ref "R10") (pin "1") (pinfunction "1_1") (pintype "passive"))
      (node (ref "R17") (pin "1") (pinfunction "1_1") (pintype "passive"))
      (node (ref "R23") (pin "1") (pinfunction "1_1") (pintype "passive"))
      (node (ref "R28") (pin "1") (pinfunction "1_1") (pintype "passive"))
      (node (ref "R8") (pin "2") (pinfunction "2_2") (pintype "passive"))
      (node (ref "R9") (pin "1") (pinfunction "1_1") (pintype "passive"))
      (node (ref "U1") (pin "2") (pinfunction "GND_2") (pintype "passive"))
      (node (ref "U2") (pin "2") (pinfunction "SwE_2") (pintype "passive"))
      (node (ref "U2") (pin "4") (pinfunction "GND_4") (pintype "passive"))
      (node (ref "U3") (pin "1") (pinfunction "GND_1") (pintype "passive"))
      (node (ref "U3") (pin "9") (pinfunction "GND_9") (pintype "passive"))
      (node (ref "U4") (pin "2") (pinfunction "GND_2") (pintype "passive"))
      (node (ref "U5") (pin "23") (pinfunction "VSS_1_23") (pintype "power_in"))
      (node (ref "U5") (pin "35") (pinfunction "VSS_2_35") (pintype "power_in"))
      (node (ref "U5") (pin "47") (pinfunction "VSS_3_47") (pintype "power_in"))
      (node (ref "U5") (pin "8") (pinfunction "VSSA_8") (pintype "power_in"))
      (node (ref "U6") (pin "1") (pinfunction "A0_1") (pintype "passive"))
      (node (ref "U6") (pin "2") (pinfunction "A1_2") (pintype "passive"))
      (node (ref "U6") (pin "3") (pinfunction "A2_3") (pintype "passive"))
      (node (ref "U6") (pin "4") (pinfunction "GND_4") (pintype "passive"))
      (node (ref "U6") (pin "7") (pinfunction "WP_7") (pintype "passive"))
      (node (ref "U7") (pin "5") (pinfunction "GND_5") (pintype "passive"))
    )
    (net (code "29") (name "Net-(D3-PadA)") (class "Default")
      (node (ref "D3") (pin "A") (pinfunction "A_A") (pintype "passive"))
      (node (ref "R1") (pin "2") (pinfunction "2_2") (pintype "passive"))
    )
    (net (code "30") (name "Net-(D7-PadA)") (class "Default")
      (node (ref "D7") (pin "A") (pinfunction "A_A") (pintype "passive"))
      (node (ref "R13") (pin "2") (pinfunction "2_2") (pintype "passive"))
    )
    (net (code "31") (name "Net-(J3-Pad2)") (class "Default")
      (node (ref "J3") (pin "2") (pinfunction "2_2") (pintype "passive"))
      (node (ref "R24") (pin "2") (pinfunction "2_2") (pintype "passive"))
    )
    (net (code "32") (name "Net-(P3-Pad2)") (class "Default")
      (node (ref "P3") (pin "2") (pinfunction "2_2") (pintype "passive"))
      (node (ref "R11") (pin "1") (pintype "passive"))
    )
    (net (code "33") (name "Net-(P3-Pad3)") (class "Default")
      (node (ref "P3") (pin "3") (pinfunction "3_3") (pintype "passive"))
      (node (ref "R12") (pin "1") (pintype "passive"))
    )
    (net (code "34") (name "Net-(Q4-D)") (class "Default")
      (node (ref "P3") (pin "1") (pinfunction "1_1") (pintype "passive"))
      (node (ref "Q4") (pin "3") (pinfunction "D_3") (pintype "passive"))
    )
    (net (code "35") (name "Net-(U1-BYP)") (class "Default")
      (node (ref "C5") (pin "2") (pinfunction "2_2") (pintype "passive"))
      (node (ref "U1") (pin "4") (pinfunction "BYP_4") (pintype "passive"))
    )
    (net (code "36") (name "Net-(U2-CII)") (class "Default")
      (node (ref "R7") (pin "1") (pinfunction "1_1") (pintype "passive"))
      (node (ref "R9") (pin "2") (pinfunction "2_2") (pintype "passive"))
      (node (ref "U2") (pin "5") (pinfunction "CII_5") (pintype "passive"))
    )
    (net (code "37") (name "Net-(U2-Drc)") (class "Default")
      (node (ref "R4") (pin "2") (pinfunction "2_2") (pintype "passive"))
      (node (ref "U2") (pin "8") (pinfunction "Drc_8") (pintype "passive"))
    )
    (net (code "38") (name "Net-(U2-Ipk)") (class "Default")
      (node (ref "L1") (pin "1") (pinfunction "1_1") (pintype "passive"))
      (node (ref "R4") (pin "1") (pinfunction "1_1") (pintype "passive"))
      (node (ref "R5") (pin "2") (pinfunction "2_2") (pintype "passive"))
      (node (ref "U2") (pin "7") (pinfunction "Ipk_7") (pintype "passive"))
    )
    (net (code "39") (name "Net-(U2-SwC)") (class "Default")
      (node (ref "D6") (pin "2") (pintype "passive"))
      (node (ref "L1") (pin "2") (pinfunction "2_2") (pintype "passive"))
      (node (ref "U2") (pin "1") (pinfunction "SwC_1") (pintype "passive"))
    )
    (net (code "40") (name "Net-(U2-TC)") (class "Default")
      (node (ref "C6") (pin "1") (pinfunction "1_1") (pintype "passive"))
      (node (ref "U2") (pin "3") (pinfunction "TC_3") (pintype "passive"))
    )
    (net (code "41") (name "Net-(U3-C1N)") (class "Default")
      (node (ref "C11") (pin "2") (pinfunction "2_2") (pintype "passive"))
      (node (ref "U3") (pin "3") (pinfunction "C1N_3") (pintype "passive"))
    )
    (net (code "42") (name "Net-(U3-C1P)") (class "Default")
      (node (ref "C11") (pin "1") (pinfunction "1_1") (pintype "passive"))
      (node (ref "U3") (pin "2") (pinfunction "C1P_2") (pintype "passive"))
    )
    (net (code "43") (name "Net-(U3-C2N)") (class "Default")
      (node (ref "C12") (pin "2") (pinfunction "2_2") (pintype "passive"))
      (node (ref "U3") (pin "8") (pinfunction "C2N_8") (pintype "passive"))
    )
    (net (code "44") (name "Net-(U3-C2P)") (class "Default")
      (node (ref "C12") (pin "1") (pinfunction "1_1") (pintype "passive"))
      (node (ref "U3") (pin "7") (pinfunction "C2P_7") (pintype "passive"))
    )
    (net (code "45") (name "Net-(U4-PROG)") (class "Default")
      (node (ref "R8") (pin "1") (pinfunction "1_1") (pintype "passive"))
      (node (ref "U4") (pin "5") (pinfunction "PROG_5") (pintype "passive"))
    )
    (net (code "46") (name "Net-(U5-BOOT1{slash}PB2)") (class "Default")
      (node (ref "R28") (pin "2") (pinfunction "2_2") (pintype "passive"))
      (node (ref "U5") (pin "20") (pinfunction "BOOT1/PB2_20") (pintype "bidirectional"))
    )
    (net (code "47") (name "Net-(U5-OSC_IN)") (class "Default")
      (node (ref "C18") (pin "2") (pinfunction "2_2") (pintype "passive"))
      (node (ref "R25") (pin "1") (pinfunction "1_1") (pintype "passive"))
      (node (ref "U5") (pin "5") (pinfunction "OSC_IN_5") (pintype "input"))
      (node (ref "X1") (pin "1") (pinfunction "OSC1_1") (pintype "passive"))
    )
    (net (code "48") (name "Net-(U5-OSC_OUT)") (class "Default")
      (node (ref "C19") (pin "2") (pinfunction "2_2") (pintype "passive"))
      (node (ref "R25") (pin "2") (pinfunction "2_2") (pintype "passive"))
      (node (ref "U5") (pin "6") (pinfunction "OSC_OUT_6") (pintype "output"))
      (node (ref "X1") (pin "2") (pinfunction "OSC2_2") (pintype "passive"))
    )
    (net (code "49") (name "Net-(U5-PA0{slash}WKUP{slash}USART2_CTS{slash}ADC12_IN0{slash}TIM2_CH1_ETR)") (class "Default")
      (node (ref "R13") (pin "1") (pinfunction "1_1") (pintype "passive"))
      (node (ref "U5") (pin "10") (pinfunction "PA0/WKUP/USART2_CTS/ADC12_IN0/TIM2_CH1_ETR_10") (pintype "bidirectional"))
    )
    (net (code "50") (name "VBAT") (class "Default")
      (node (ref "BT1") (pin "1") (pinfunction "+_1") (pintype "passive"))
      (node (ref "C4") (pin "2") (pinfunction "2_2") (pintype "passive"))
      (node (ref "D1") (pin "2") (pinfunction "K_2") (pintype "passive"))
      (node (ref "U7") (pin "6") (pinfunction "VBAT_6") (pintype "passive"))
    )
    (net (code "51") (name "VBAT_li") (class "Default")
      (node (ref "C13") (pin "2") (pinfunction "2_2") (pintype "passive"))
      (node (ref "C7") (pin "1") (pinfunction "1_1") (pintype "passive"))
      (node (ref "P2") (pin "2") (pinfunction "2_2") (pintype "passive"))
      (node (ref "R6") (pin "1") (pinfunction "1_1") (pintype "passive"))
      (node (ref "U3") (pin "4") (pinfunction "VIN_4") (pintype "passive"))
      (node (ref "U4") (pin "3") (pinfunction "BAT_3") (pintype "passive"))
    )
    (net (code "52") (name "VCC3.3V") (class "Default")
      (node (ref "C16") (pin "2") (pinfunction "2_2") (pintype "passive"))
      (node (ref "C2") (pin "1") (pinfunction "1_1") (pintype "passive"))
      (node (ref "C20") (pin "1") (pinfunction "1_1") (pintype "passive"))
      (node (ref "C21") (pin "1") (pinfunction "1_1") (pintype "passive"))
      (node (ref "C22") (pin "2") (pinfunction "2_2") (pintype "passive"))
      (node (ref "C23") (pin "2") (pinfunction "2_2") (pintype "passive"))
      (node (ref "C24") (pin "1") (pinfunction "1_1") (pintype "passive"))
      (node (ref "C25") (pin "1") (pinfunction "1_1") (pintype "passive"))
      (node (ref "C26") (pin "1") (pinfunction "1_1") (pintype "passive"))
      (node (ref "C27") (pin "1") (pinfunction "1_1") (pintype "passive"))
      (node (ref "C28") (pin "1") (pinfunction "1_1") (pintype "passive"))
      (node (ref "C29") (pin "1") (pinfunction "1_1") (pintype "passive"))
      (node (ref "C3") (pin "2") (pinfunction "2_2") (pintype "passive"))
      (node (ref "D1") (pin "1") (pinfunction "A_1") (pintype "passive"))
      (node (ref "J2") (pin "1") (pinfunction "1_1") (pintype "passive"))
      (node (ref "J3") (pin "1") (pinfunction "1_1") (pintype "passive"))
      (node (ref "P5") (pin "1") (pinfunction "1_1") (pintype "passive"))
      (node (ref "P6") (pin "3") (pinfunction "3_3") (pintype "passive"))
      (node (ref "P7") (pin "1") (pinfunction "1_1") (pintype "passive"))
      (node (ref "P9") (pin "3") (pinfunction "3_3") (pintype "passive"))
      (node (ref "Q4") (pin "2") (pinfunction "S_2") (pintype "passive"))
      (node (ref "R1") (pin "1") (pinfunction "1_1") (pintype "passive"))
      (node (ref "R14") (pin "1") (pintype "passive"))
      (node (ref "R15") (pin "1") (pintype "passive"))
      (node (ref "R16") (pin "1") (pintype "passive"))
      (node (ref "R18") (pin "1") (pintype "passive"))
      (node (ref "R19") (pin "1") (pintype "passive"))
      (node (ref "R20") (pin "1") (pintype "passive"))
      (node (ref "R21") (pin "1") (pinfunction "1_1") (pintype "passive"))
      (node (ref "R22") (pin "2") (pinfunction "2_2") (pintype "passive"))
      (node (ref "R30") (pin "1") (pintype "passive"))
      (node (ref "R32") (pin "2") (pinfunction "2_2") (pintype "passive"))
      (node (ref "U1") (pin "5") (pinfunction "Vout_5") (pintype "passive"))
      (node (ref "U5") (pin "1") (pinfunction "VBAT_1") (pintype "power_in"))
      (node (ref "U5") (pin "24") (pinfunction "VDD_1_24") (pintype "power_in"))
      (node (ref "U5") (pin "36") (pinfunction "VDD_2_36") (pintype "power_in"))
      (node (ref "U5") (pin "48") (pinfunction "VDD_3_48") (pintype "power_in"))
      (node (ref "U5") (pin "9") (pinfunction "VDDA_9") (pintype "power_in"))
      (node (ref "U6") (pin "8") (pinfunction "VCC_8") (pintype "passive"))
      (node (ref "U7") (pin "2") (pinfunction "Vcc_2") (pintype "passive"))
    )
    (net (code "53") (name "VCC5V") (class "Default")
      (node (ref "C1") (pin "1") (pinfunction "1_1") (pintype "passive"))
      (node (ref "C10") (pin "2") (pinfunction "2_2") (pintype "passive"))
      (node (ref "C8") (pin "1") (pintype "passive"))
      (node (ref "C9") (pin "1") (pinfunction "1_1") (pintype "passive"))
      (node (ref "D2") (pin "2") (pinfunction "K_2") (pintype "passive"))
      (node (ref "P8") (pin "5") (pinfunction "5_5") (pintype "passive"))
      (node (ref "R29") (pin "1") (pinfunction "1_1") (pintype "passive"))
      (node (ref "R5") (pin "1") (pinfunction "1_1") (pintype "passive"))
      (node (ref "U1") (pin "1") (pinfunction "Vin_1") (pintype "passive"))
      (node (ref "U1") (pin "3") (pinfunction "EN_3") (pintype "passive"))
      (node (ref "U2") (pin "6") (pinfunction "VCC_6") (pintype "passive"))
      (node (ref "U3") (pin "6") (pinfunction "OUT_6") (pintype "passive"))
    )
    (net (code "54") (name "VCC35V") (class "Default")
      (node (ref "C14") (pin "2") (pinfunction "2_2") (pintype "passive"))
      (node (ref "C15") (pin "1") (pintype "passive"))
      (node (ref "D6") (pin "1") (pintype "passive"))
      (node (ref "P8") (pin "7") (pinfunction "7_7") (pintype "passive"))
      (node (ref "R7") (pin "2") (pinfunction "2_2") (pintype "passive"))
    )
    (net (code "55") (name "unconnected-(J1-D+-Pad2)") (class "Default")
      (node (ref "J1") (pin "2") (pinfunction "D+_2") (pintype "passive"))
    )
    (net (code "56") (name "unconnected-(J1-D--Pad3)") (class "Default")
      (node (ref "J1") (pin "3") (pinfunction "D-_3") (pintype "passive"))
    )
    (net (code "57") (name "unconnected-(U4-~{CHRG}-Pad1)") (class "Default")
      (node (ref "U4") (pin "1") (pinfunction "~{CHRG}_1") (pintype "passive"))
    )
    (net (code "58") (name "unconnected-(U5-JNTRST{slash}PB4-Pad40)") (class "Default")
      (node (ref "U5") (pin "40") (pinfunction "JNTRST/PB4_40") (pintype "bidirectional"))
    )
    (net (code "59") (name "unconnected-(U5-JTDO{slash}PB3-Pad39)") (class "Default")
      (node (ref "U5") (pin "39") (pinfunction "JTDO/PB3_39") (pintype "bidirectional"))
    )
    (net (code "60") (name "unconnected-(U5-PA8{slash}USART1_CK{slash}TIM1_CH1{slash}MCO-Pad29)") (class "Default")
      (node (ref "U5") (pin "29") (pinfunction "PA8/USART1_CK/TIM1_CH1/MCO_29") (pintype "bidirectional"))
    )
    (net (code "61") (name "unconnected-(U5-PA11{slash}USART1_CTS{slash}CANRX{slash}TIM1_CH4{slash}USBDM-Pad32)") (class "Default")
      (node (ref "U5") (pin "32") (pinfunction "PA11/USART1_CTS/CANRX/TIM1_CH4/USBDM_32") (pintype "bidirectional"))
    )
    (net (code "62") (name "unconnected-(U5-PA12{slash}USART1_RTS{slash}CANTX{slash}TIM1_ETR{slash}USBDP-Pad33)") (class "Default")
      (node (ref "U5") (pin "33") (pinfunction "PA12/USART1_RTS/CANTX/TIM1_ETR/USBDP_33") (pintype "bidirectional"))
    )
    (net (code "63") (name "unconnected-(U5-PA15{slash}JTDI-Pad38)") (class "Default")
      (node (ref "U5") (pin "38") (pinfunction "PA15/JTDI_38") (pintype "bidirectional"))
    )
    (net (code "64") (name "unconnected-(U5-PC13-TAMPER-RTC-Pad2)") (class "Default")
      (node (ref "U5") (pin "2") (pinfunction "PC13-TAMPER-RTC_2") (pintype "bidirectional"))
    )
    (net (code "65") (name "unconnected-(U5-PC14-OSC32_IN-Pad3)") (class "Default")
      (node (ref "U5") (pin "3") (pinfunction "PC14-OSC32_IN_3") (pintype "bidirectional+no_connect"))
    )
    (net (code "66") (name "unconnected-(U5-PC15-OSC32_OUT-Pad4)") (class "Default")
      (node (ref "U5") (pin "4") (pinfunction "PC15-OSC32_OUT_4") (pintype "bidirectional+no_connect"))
    )
    (net (code "67") (name "unconnected-(U5-TIM3_CH4{slash}ADC12_IN9{slash}PB1-Pad19)") (class "Default")
      (node (ref "U5") (pin "19") (pinfunction "TIM3_CH4/ADC12_IN9/PB1_19") (pintype "bidirectional"))
    )
    (net (code "68") (name "unconnected-(U5-TIM4_CH4{slash}PB9-Pad46)") (class "Default")
      (node (ref "U5") (pin "46") (pinfunction "TIM4_CH4/PB9_46") (pintype "bidirectional"))
    )
    (net (code "69") (name "unconnected-(U7-32KHz-Pad1)") (class "Default")
      (node (ref "U7") (pin "1") (pinfunction "32KHz_1") (pintype "passive"))
    )
    (net (code "70") (name "unconnected-(U7-~{INT}{slash}SQW-Pad3)") (class "Default")
      (node (ref "U7") (pin "3") (pinfunction "~{INT}/SQW_3") (pintype "passive"))
    )
  )
)
